# JFET_meter.net
KiCad netlist of a schematic drawn in EAGLE
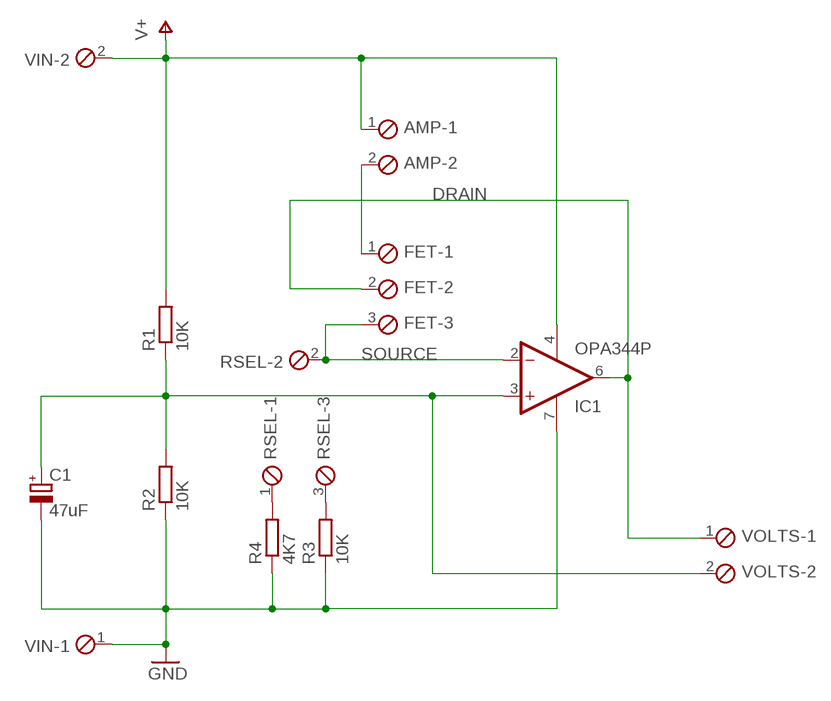
[diagram p0: schematic, sheet 1]

(export (version "E")
  (design (tool "Eeschema 10.0.6"))
  (components
    (comp (ref "AMP")
      (value "MPT2")
      (footprint "eagle-import:2POL254")
      (libsource (lib "eagle-import") (part "MPT2"))
    )
    (comp (ref "C1")
      (value "47uF")
      (footprint "eagle-import:E5-10,5")
      (libsource (lib "eagle-import") (part "CPOL-EUE5-10.5"))
    )
    (comp (ref "FET")
      (value "MPT3")
      (footprint "eagle-import:3POL254")
      (libsource (lib "eagle-import") (part "MPT3"))
    )
    (comp (ref "IC1")
      (value "OPA344P")
      (footprint "eagle-import:DIL08")
      (libsource (lib "eagle-import") (part "OPAP344"))
    )
    (comp (ref "R1")
      (value "10K")
      (footprint "eagle-import:0207_10")
      (libsource (lib "eagle-import") (part "R-EU_0207/10"))
    )
    (comp (ref "R2")
      (value "10K")
      (footprint "eagle-import:0207_10")
      (libsource (lib "eagle-import") (part "R-EU_0207/10"))
    )
    (comp (ref "R3")
      (value "10K")
      (footprint "eagle-import:0207_10")
      (libsource (lib "eagle-import") (part "R-EU_0207/10"))
    )
    (comp (ref "R4")
      (value "4K7")
      (footprint "eagle-import:0207_10")
      (libsource (lib "eagle-import") (part "R-EU_0207/10"))
    )
    (comp (ref "RSEL")
      (value "MPT3")
      (footprint "eagle-import:3POL254")
      (libsource (lib "eagle-import") (part "MPT3"))
    )
    (comp (ref "VIN")
      (value "MPT2")
      (footprint "eagle-import:2POL254")
      (libsource (lib "eagle-import") (part "MPT2"))
    )
    (comp (ref "VOLTS")
      (value "MPT2")
      (footprint "eagle-import:2POL254")
      (libsource (lib "eagle-import") (part "MPT2"))
    )
  )
  (nets
    (net (code "1") (name "/DRAIN") (class "Default")
      (node (ref "AMP") (pin "2") (pinfunction "1_2") (pintype "passive"))
      (node (ref "FET") (pin "1") (pinfunction "1_1") (pintype "passive"))
    )
    (net (code "2") (name "/SOURCE") (class "Default")
      (node (ref "FET") (pin "3") (pinfunction "1_3") (pintype "passive"))
      (node (ref "IC1") (pin "2") (pinfunction "-IN_2") (pintype "input"))
      (node (ref "RSEL") (pin "2") (pinfunction "1_2") (pintype "passive"))
    )
    (net (code "3") (name "GND") (class "Default")
      (node (ref "C1") (pin "-") (pinfunction "-_-") (pintype "passive"))
      (node (ref "IC1") (pin "7") (pinfunction "V+_7") (pintype "power_in"))
      (node (ref "R2") (pin "1") (pinfunction "1_1") (pintype "passive"))
      (node (ref "R3") (pin "1") (pinfunction "1_1") (pintype "passive"))
      (node (ref "R4") (pin "1") (pinfunction "1_1") (pintype "passive"))
      (node (ref "VIN") (pin "1") (pinfunction "1_1") (pintype "passive"))
    )
    (net (code "4") (name "Net-(FETB-1)") (class "Default")
      (node (ref "FET") (pin "2") (pinfunction "1_2") (pintype "passive"))
      (node (ref "IC1") (pin "6") (pinfunction "OUT_6") (pintype "output"))
      (node (ref "VOLTS") (pin "1") (pinfunction "1_1") (pintype "passive"))
    )
    (net (code "5") (name "Net-(IC1-+IN)") (class "Default")
      (node (ref "C1") (pin "+") (pinfunction "+_+") (pintype "passive"))
      (node (ref "IC1") (pin "3") (pinfunction "+IN_3") (pintype "input"))
      (node (ref "R1") (pin "1") (pinfunction "1_1") (pintype "passive"))
      (node (ref "R2") (pin "2") (pinfunction "2_2") (pintype "passive"))
      (node (ref "VOLTS") (pin "2") (pinfunction "1_2") (pintype "passive"))
    )
    (net (code "6") (name "Net-(R4-Pad2)") (class "Default")
      (node (ref "R4") (pin "2") (pinfunction "2_2") (pintype "passive"))
      (node (ref "RSEL") (pin "1") (pinfunction "1_1") (pintype "passive"))
    )
    (net (code "7") (name "Net-(RSELC-1)") (class "Default")
      (node (ref "R3") (pin "2") (pinfunction "2_2") (pintype "passive"))
      (node (ref "RSEL") (pin "3") (pinfunction "1_3") (pintype "passive"))
    )
    (net (code "8") (name "V+") (class "Default")
      (node (ref "AMP") (pin "1") (pinfunction "1_1") (pintype "passive"))
      (node (ref "IC1") (pin "4") (pinfunction "V-_4") (pintype "power_in"))
      (node (ref "R1") (pin "2") (pinfunction "2_2") (pintype "passive"))
      (node (ref "VIN") (pin "2") (pinfunction "1_2") (pintype "passive"))
    )
  )
)
